# untitled.net
KiCad netlist of a schematic drawn in EAGLE
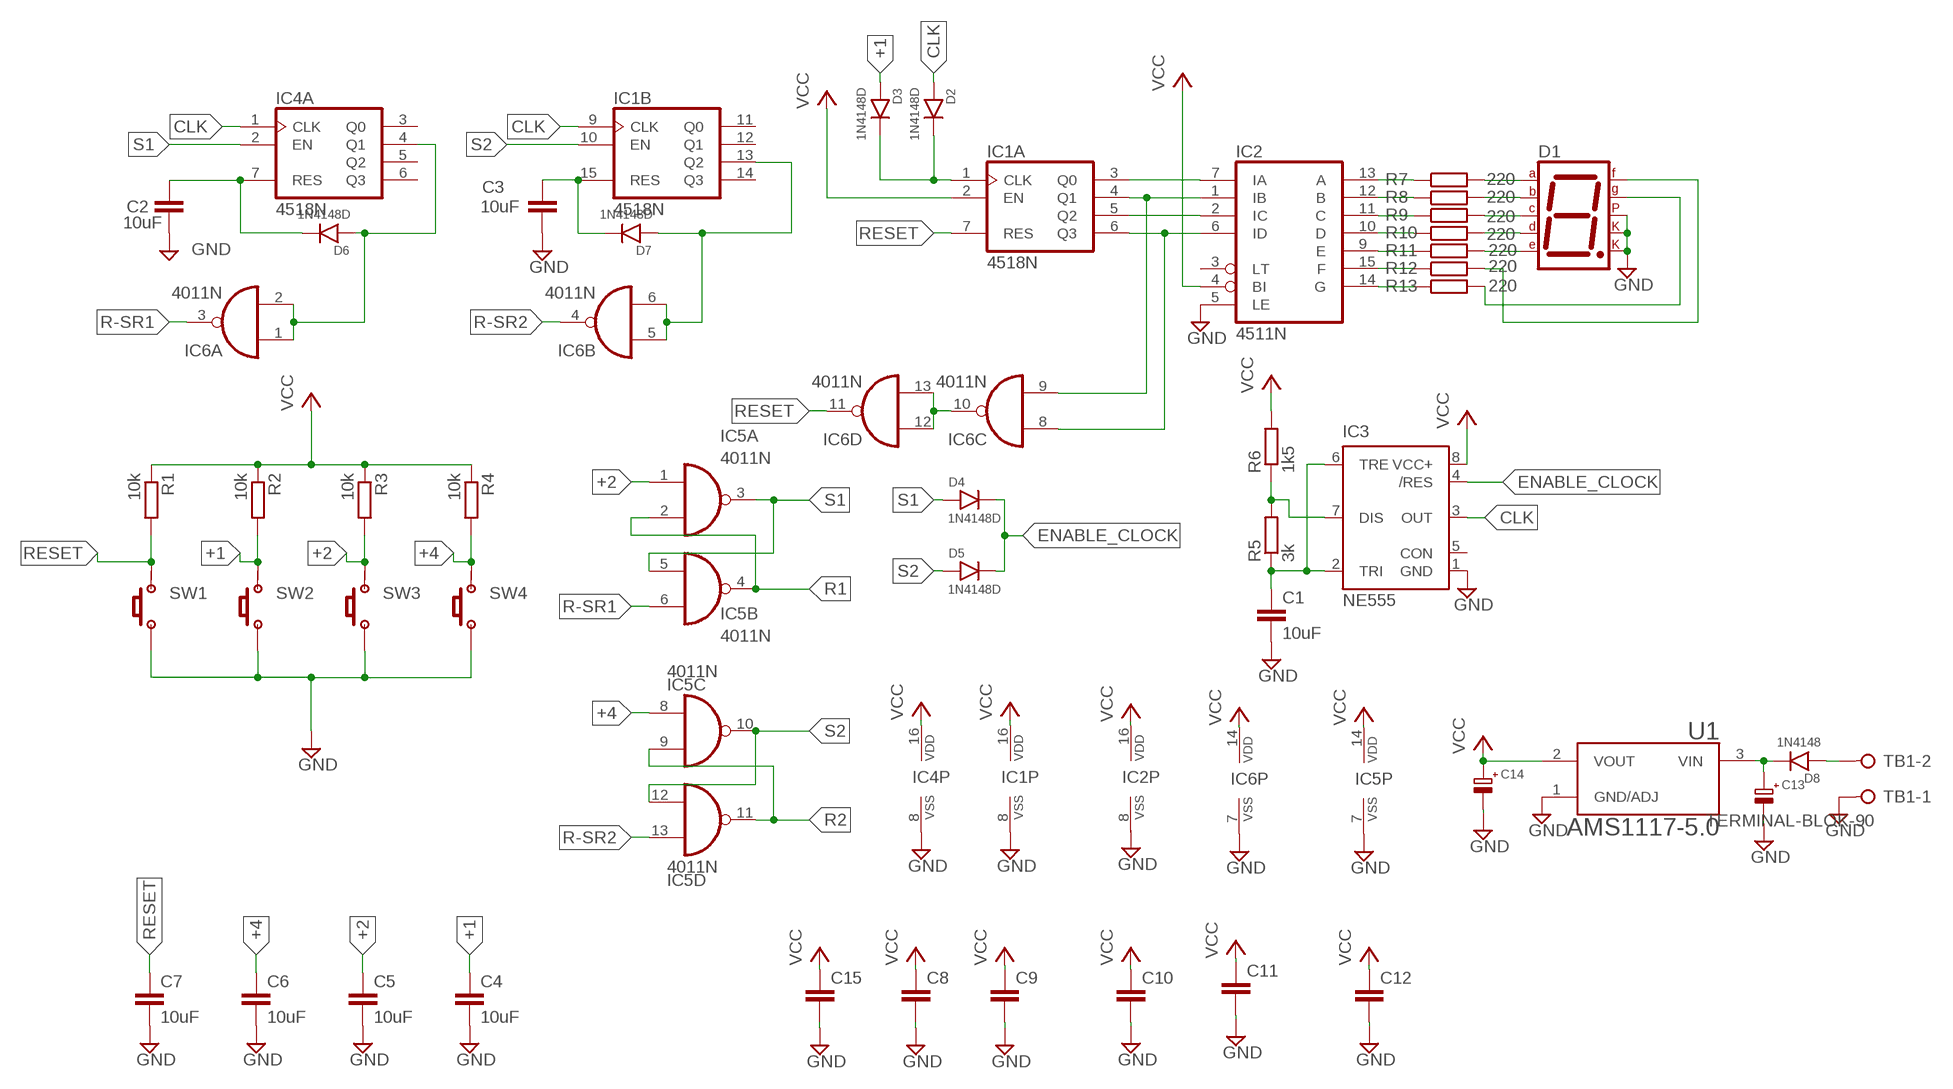
[diagram p0: schematic, sheet 1]

(export (version "E")
  (design (tool "Eeschema 10.0.6"))
  (components
    (comp (ref "C1")
      (value "10uF")
      (footprint "eagle-import:SMD0805")
      (libsource (lib "eagle-import") (part "CAP-NON0805"))
    )
    (comp (ref "C2")
      (value "10uF")
      (footprint "eagle-import:SMD0805")
      (libsource (lib "eagle-import") (part "CAP-NON0805"))
    )
    (comp (ref "C3")
      (value "10uF")
      (footprint "eagle-import:SMD0805")
      (libsource (lib "eagle-import") (part "CAP-NON0805"))
    )
    (comp (ref "C4")
      (value "10uF")
      (footprint "eagle-import:SMD0805")
      (libsource (lib "eagle-import") (part "CAP-NON0805"))
    )
    (comp (ref "C5")
      (value "10uF")
      (footprint "eagle-import:SMD0805")
      (libsource (lib "eagle-import") (part "CAP-NON0805"))
    )
    (comp (ref "C6")
      (value "10uF")
      (footprint "eagle-import:SMD0805")
      (libsource (lib "eagle-import") (part "CAP-NON0805"))
    )
    (comp (ref "C7")
      (value "10uF")
      (footprint "eagle-import:SMD0805")
      (libsource (lib "eagle-import") (part "CAP-NON0805"))
    )
    (comp (ref "C8")
      (value "CAP-NON")
      (footprint "eagle-import:MKM")
      (libsource (lib "eagle-import") (part "CAP-NON"))
    )
    (comp (ref "C9")
      (value "CAP-NON")
      (footprint "eagle-import:MKM")
      (libsource (lib "eagle-import") (part "CAP-NON"))
    )
    (comp (ref "C10")
      (value "CAP-NON")
      (footprint "eagle-import:MKM")
      (libsource (lib "eagle-import") (part "CAP-NON"))
    )
    (comp (ref "C11")
      (value "CAP-NON")
      (footprint "eagle-import:MKM")
      (libsource (lib "eagle-import") (part "CAP-NON"))
    )
    (comp (ref "C12")
      (value "CAP-NON")
      (footprint "eagle-import:MKM")
      (libsource (lib "eagle-import") (part "CAP-NON"))
    )
    (comp (ref "C13")
      (value "CAP-ELCO")
      (footprint "eagle-import:ELCO1")
      (libsource (lib "eagle-import") (part "CAP-ELCO"))
    )
    (comp (ref "C14")
      (value "CAP-ELCO")
      (footprint "eagle-import:ELCO1")
      (libsource (lib "eagle-import") (part "CAP-ELCO"))
    )
    (comp (ref "C15")
      (value "CAP-NON")
      (footprint "eagle-import:MKM")
      (libsource (lib "eagle-import") (part "CAP-NON"))
    )
    (comp (ref "D1")
      (value "7SEG-CK")
      (footprint "eagle-import:7SEG-13")
      (libsource (lib "eagle-import") (part "7SEG-CK"))
    )
    (comp (ref "D2")
      (value "1N4148D")
      (footprint "eagle-import:SOD80C")
      (libsource (lib "eagle-import") (part "1N4148D"))
    )
    (comp (ref "D3")
      (value "1N4148D")
      (footprint "eagle-import:SOD80C")
      (libsource (lib "eagle-import") (part "1N4148D"))
    )
    (comp (ref "D4")
      (value "1N4148D")
      (footprint "eagle-import:SOD80C")
      (libsource (lib "eagle-import") (part "1N4148D"))
    )
    (comp (ref "D5")
      (value "1N4148D")
      (footprint "eagle-import:SOD80C")
      (libsource (lib "eagle-import") (part "1N4148D"))
    )
    (comp (ref "D6")
      (value "1N4148D")
      (footprint "eagle-import:SOD80C")
      (libsource (lib "eagle-import") (part "1N4148D"))
    )
    (comp (ref "D7")
      (value "1N4148D")
      (footprint "eagle-import:SOD80C")
      (libsource (lib "eagle-import") (part "1N4148D"))
    )
    (comp (ref "D8")
      (value "1N4148")
      (footprint "eagle-import:DIODE")
      (libsource (lib "eagle-import") (part "1N4148"))
    )
    (comp (ref "IC1")
      (value "4518N")
      (footprint "eagle-import:DIL16")
      (libsource (lib "eagle-import") (part "4518N"))
    )
    (comp (ref "IC2")
      (value "4511N")
      (footprint "eagle-import:DIL16")
      (libsource (lib "eagle-import") (part "4511N"))
    )
    (comp (ref "IC3")
      (value "NE555")
      (footprint "eagle-import:DIL-08")
      (fields (field (name "MF") "Arrow Electronics") (field (name "MPN") "NE555N"))
      (libsource (lib "eagle-import") (part "NE555"))
    )
    (comp (ref "IC4")
      (value "4518N")
      (footprint "eagle-import:DIL16")
      (libsource (lib "eagle-import") (part "4518N"))
    )
    (comp (ref "IC5")
      (value "4011N")
      (footprint "eagle-import:DIL14")
      (libsource (lib "eagle-import") (part "4011N"))
    )
    (comp (ref "IC6")
      (value "4011N")
      (footprint "eagle-import:DIL14")
      (libsource (lib "eagle-import") (part "4011N"))
    )
    (comp (ref "R1")
      (value "10k")
      (footprint "eagle-import:SMD0805")
      (libsource (lib "eagle-import") (part "RES0805"))
    )
    (comp (ref "R2")
      (value "10k")
      (footprint "eagle-import:SMD0805")
      (libsource (lib "eagle-import") (part "RES0805"))
    )
    (comp (ref "R3")
      (value "10k")
      (footprint "eagle-import:SMD0805")
      (libsource (lib "eagle-import") (part "RES0805"))
    )
    (comp (ref "R4")
      (value "10k")
      (footprint "eagle-import:SMD0805")
      (libsource (lib "eagle-import") (part "RES0805"))
    )
    (comp (ref "R5")
      (value "3k")
      (footprint "eagle-import:SMD0805")
      (libsource (lib "eagle-import") (part "RES0805"))
    )
    (comp (ref "R6")
      (value "1k5")
      (footprint "eagle-import:SMD0805")
      (libsource (lib "eagle-import") (part "RES0805"))
    )
    (comp (ref "R7")
      (value "220")
      (footprint "eagle-import:SMD0805")
      (libsource (lib "eagle-import") (part "RES0805"))
    )
    (comp (ref "R8")
      (value "220")
      (footprint "eagle-import:SMD0805")
      (libsource (lib "eagle-import") (part "RES0805"))
    )
    (comp (ref "R9")
      (value "220")
      (footprint "eagle-import:SMD0805")
      (libsource (lib "eagle-import") (part "RES0805"))
    )
    (comp (ref "R10")
      (value "220")
      (footprint "eagle-import:SMD0805")
      (libsource (lib "eagle-import") (part "RES0805"))
    )
    (comp (ref "R11")
      (value "220")
      (footprint "eagle-import:SMD0805")
      (libsource (lib "eagle-import") (part "RES0805"))
    )
    (comp (ref "R12")
      (value "220")
      (footprint "eagle-import:SMD0805")
      (libsource (lib "eagle-import") (part "RES0805"))
    )
    (comp (ref "R13")
      (value "220")
      (footprint "eagle-import:SMD0805")
      (libsource (lib "eagle-import") (part "RES0805"))
    )
    (comp (ref "SW1")
      (value "PUSH_BUTTON4P")
      (footprint "eagle-import:PUSH_BUTTON_4P")
      (libsource (lib "eagle-import") (part "PUSH_BUTTON4P"))
    )
    (comp (ref "SW2")
      (value "PUSH_BUTTON4P")
      (footprint "eagle-import:PUSH_BUTTON_4P")
      (libsource (lib "eagle-import") (part "PUSH_BUTTON4P"))
    )
    (comp (ref "SW3")
      (value "PUSH_BUTTON4P")
      (footprint "eagle-import:PUSH_BUTTON_4P")
      (libsource (lib "eagle-import") (part "PUSH_BUTTON4P"))
    )
    (comp (ref "SW4")
      (value "PUSH_BUTTON4P")
      (footprint "eagle-import:PUSH_BUTTON_4P")
      (libsource (lib "eagle-import") (part "PUSH_BUTTON4P"))
    )
    (comp (ref "TB1")
      (value "TERMINAL-BLOK-90")
      (footprint "eagle-import:MSTBA2")
      (libsource (lib "eagle-import") (part "TERMINAL-BLOK-90"))
    )
    (comp (ref "U1")
      (value "AMS1117-5.0")
      (footprint "eagle-import:SOT229P700X180-4N")
      (libsource (lib "eagle-import") (part "AMS1117-5.0"))
    )
  )
  (nets
    (net (code "1") (name "+1") (class "Default")
      (node (ref "C4") (pin "1") (pinfunction "1_1") (pintype "passive"))
      (node (ref "D3") (pin "A") (pinfunction "1_A") (pintype "bidirectional"))
      (node (ref "R2") (pin "2") (pinfunction "2_2") (pintype "passive"))
      (node (ref "SW2") (pin "3") (pinfunction "2_3") (pintype "bidirectional"))
      (node (ref "SW2") (pin "4") (pinfunction "2_4") (pintype "bidirectional"))
    )
    (net (code "2") (name "+2") (class "Default")
      (node (ref "C5") (pin "1") (pinfunction "1_1") (pintype "passive"))
      (node (ref "IC5") (pin "1") (pinfunction "I0_1") (pintype "input"))
      (node (ref "R3") (pin "2") (pinfunction "2_2") (pintype "passive"))
      (node (ref "SW3") (pin "3") (pinfunction "2_3") (pintype "bidirectional"))
      (node (ref "SW3") (pin "4") (pinfunction "2_4") (pintype "bidirectional"))
    )
    (net (code "3") (name "+4") (class "Default")
      (node (ref "C6") (pin "1") (pinfunction "1_1") (pintype "passive"))
      (node (ref "IC5") (pin "8") (pinfunction "I0_8") (pintype "input"))
      (node (ref "R4") (pin "2") (pinfunction "2_2") (pintype "passive"))
      (node (ref "SW4") (pin "3") (pinfunction "2_3") (pintype "bidirectional"))
      (node (ref "SW4") (pin "4") (pinfunction "2_4") (pintype "bidirectional"))
    )
    (net (code "4") (name "/VSS") (class "Default")
      (node (ref "IC2") (pin "8") (pinfunction "VSS_8") (pintype "power_in"))
    )
    (net (code "5") (name "CLK") (class "Default")
      (node (ref "D2") (pin "A") (pinfunction "1_A") (pintype "bidirectional"))
      (node (ref "IC1") (pin "9") (pinfunction "CLK_9") (pintype "input"))
      (node (ref "IC3") (pin "3") (pinfunction "OUT_3") (pintype "output"))
      (node (ref "IC4") (pin "1") (pinfunction "CLK_1") (pintype "input"))
    )
    (net (code "6") (name "ENABLE_CLOCK") (class "Default")
      (node (ref "D4") (pin "C") (pinfunction "2_C") (pintype "bidirectional"))
      (node (ref "D5") (pin "C") (pinfunction "2_C") (pintype "bidirectional"))
      (node (ref "IC3") (pin "4") (pinfunction "/RES_4") (pintype "input"))
    )
    (net (code "7") (name "GND") (class "Default")
      (node (ref "C1") (pin "2") (pinfunction "2_2") (pintype "passive"))
      (node (ref "C10") (pin "2") (pinfunction "2_2") (pintype "passive"))
      (node (ref "C11") (pin "2") (pinfunction "2_2") (pintype "passive"))
      (node (ref "C12") (pin "2") (pinfunction "2_2") (pintype "passive"))
      (node (ref "C13") (pin "2") (pinfunction "2_2") (pintype "bidirectional"))
      (node (ref "C14") (pin "2") (pinfunction "2_2") (pintype "bidirectional"))
      (node (ref "C15") (pin "2") (pinfunction "2_2") (pintype "passive"))
      (node (ref "C2") (pin "2") (pinfunction "2_2") (pintype "passive"))
      (node (ref "C3") (pin "2") (pinfunction "2_2") (pintype "passive"))
      (node (ref "C4") (pin "2") (pinfunction "2_2") (pintype "passive"))
      (node (ref "C5") (pin "2") (pinfunction "2_2") (pintype "passive"))
      (node (ref "C6") (pin "2") (pinfunction "2_2") (pintype "passive"))
      (node (ref "C7") (pin "2") (pinfunction "2_2") (pintype "passive"))
      (node (ref "C8") (pin "2") (pinfunction "2_2") (pintype "passive"))
      (node (ref "C9") (pin "2") (pinfunction "2_2") (pintype "passive"))
      (node (ref "D1") (pin "3") (pinfunction "CK1_3") (pintype "passive"))
      (node (ref "D1") (pin "5") (pinfunction "DP_5") (pintype "passive"))
      (node (ref "D1") (pin "8") (pinfunction "CK2_8") (pintype "passive"))
      (node (ref "IC1") (pin "8") (pinfunction "VSS_8") (pintype "power_in"))
      (node (ref "IC2") (pin "5") (pinfunction "LE_5") (pintype "input"))
      (node (ref "IC3") (pin "1") (pinfunction "GND_1") (pintype "power_in"))
      (node (ref "IC4") (pin "8") (pinfunction "VSS_8") (pintype "power_in"))
      (node (ref "IC5") (pin "7") (pinfunction "VSS_7") (pintype "power_in"))
      (node (ref "IC6") (pin "7") (pinfunction "VSS_7") (pintype "power_in"))
      (node (ref "SW1") (pin "1") (pinfunction "1_1") (pintype "bidirectional"))
      (node (ref "SW1") (pin "2") (pinfunction "1_2") (pintype "bidirectional"))
      (node (ref "SW2") (pin "1") (pinfunction "1_1") (pintype "bidirectional"))
      (node (ref "SW2") (pin "2") (pinfunction "1_2") (pintype "bidirectional"))
      (node (ref "SW3") (pin "1") (pinfunction "1_1") (pintype "bidirectional"))
      (node (ref "SW3") (pin "2") (pinfunction "1_2") (pintype "bidirectional"))
      (node (ref "SW4") (pin "1") (pinfunction "1_1") (pintype "bidirectional"))
      (node (ref "SW4") (pin "2") (pinfunction "1_2") (pintype "bidirectional"))
      (node (ref "TB1") (pin "1") (pinfunction "KL_1") (pintype "passive"))
      (node (ref "U1") (pin "1") (pinfunction "GND/ADJ_1") (pintype "power_in"))
    )
    (net (code "8") (name "Net-(D1-A)") (class "Default")
      (node (ref "D1") (pin "7") (pinfunction "A_7") (pintype "passive"))
      (node (ref "R7") (pin "2") (pinfunction "2_2") (pintype "passive"))
    )
    (net (code "9") (name "Net-(D1-B)") (class "Default")
      (node (ref "D1") (pin "6") (pinfunction "B_6") (pintype "passive"))
      (node (ref "R8") (pin "2") (pinfunction "2_2") (pintype "passive"))
    )
    (net (code "10") (name "Net-(D1-C)") (class "Default")
      (node (ref "D1") (pin "4") (pinfunction "C_4") (pintype "passive"))
      (node (ref "R9") (pin "2") (pinfunction "2_2") (pintype "passive"))
    )
    (net (code "11") (name "Net-(D1-D)") (class "Default")
      (node (ref "D1") (pin "2") (pinfunction "D_2") (pintype "passive"))
      (node (ref "R10") (pin "2") (pinfunction "2_2") (pintype "passive"))
    )
    (net (code "12") (name "Net-(D1-E)") (class "Default")
      (node (ref "D1") (pin "1") (pinfunction "E_1") (pintype "passive"))
      (node (ref "R11") (pin "2") (pinfunction "2_2") (pintype "passive"))
    )
    (net (code "13") (name "Net-(D1-F)") (class "Default")
      (node (ref "D1") (pin "9") (pinfunction "F_9") (pintype "passive"))
      (node (ref "R12") (pin "2") (pinfunction "2_2") (pintype "passive"))
    )
    (net (code "14") (name "Net-(D1-G)") (class "Default")
      (node (ref "D1") (pin "10") (pinfunction "G_10") (pintype "passive"))
      (node (ref "R13") (pin "2") (pinfunction "2_2") (pintype "passive"))
    )
    (net (code "15") (name "Net-(D2-2)") (class "Default")
      (node (ref "D2") (pin "C") (pinfunction "2_C") (pintype "bidirectional"))
      (node (ref "D3") (pin "C") (pinfunction "2_C") (pintype "bidirectional"))
      (node (ref "IC1") (pin "1") (pinfunction "CLK_1") (pintype "input"))
    )
    (net (code "16") (name "Net-(D6-1)") (class "Default")
      (node (ref "D6") (pin "A") (pinfunction "1_A") (pintype "bidirectional"))
      (node (ref "IC4") (pin "4") (pinfunction "Q1_4") (pintype "output"))
      (node (ref "IC6") (pin "1") (pinfunction "I0_1") (pintype "input"))
      (node (ref "IC6") (pin "2") (pinfunction "I1_2") (pintype "input"))
    )
    (net (code "17") (name "Net-(D6-2)") (class "Default")
      (node (ref "C2") (pin "1") (pinfunction "1_1") (pintype "passive"))
      (node (ref "D6") (pin "C") (pinfunction "2_C") (pintype "bidirectional"))
      (node (ref "IC4") (pin "7") (pinfunction "RES_7") (pintype "input"))
    )
    (net (code "18") (name "Net-(D7-1)") (class "Default")
      (node (ref "D7") (pin "A") (pinfunction "1_A") (pintype "bidirectional"))
      (node (ref "IC1") (pin "13") (pinfunction "Q2_13") (pintype "output"))
      (node (ref "IC6") (pin "5") (pinfunction "I0_5") (pintype "input"))
      (node (ref "IC6") (pin "6") (pinfunction "I1_6") (pintype "input"))
    )
    (net (code "19") (name "Net-(D7-2)") (class "Default")
      (node (ref "C3") (pin "1") (pinfunction "1_1") (pintype "passive"))
      (node (ref "D7") (pin "C") (pinfunction "2_C") (pintype "bidirectional"))
      (node (ref "IC1") (pin "15") (pinfunction "RES_15") (pintype "input"))
    )
    (net (code "20") (name "Net-(IC1A-Q0)") (class "Default")
      (node (ref "IC1") (pin "3") (pinfunction "Q0_3") (pintype "output"))
      (node (ref "IC2") (pin "7") (pinfunction "IA_7") (pintype "input"))
    )
    (net (code "21") (name "Net-(IC1A-Q1)") (class "Default")
      (node (ref "IC1") (pin "4") (pinfunction "Q1_4") (pintype "output"))
      (node (ref "IC2") (pin "1") (pinfunction "IB_1") (pintype "input"))
      (node (ref "IC6") (pin "9") (pinfunction "I1_9") (pintype "input"))
    )
    (net (code "22") (name "Net-(IC1A-Q2)") (class "Default")
      (node (ref "IC1") (pin "5") (pinfunction "Q2_5") (pintype "output"))
      (node (ref "IC2") (pin "2") (pinfunction "IC_2") (pintype "input"))
    )
    (net (code "23") (name "Net-(IC1A-Q3)") (class "Default")
      (node (ref "IC1") (pin "6") (pinfunction "Q3_6") (pintype "output"))
      (node (ref "IC2") (pin "6") (pinfunction "ID_6") (pintype "input"))
      (node (ref "IC6") (pin "8") (pinfunction "I0_8") (pintype "input"))
    )
    (net (code "24") (name "Net-(IC2A-A)") (class "Default")
      (node (ref "IC2") (pin "13") (pinfunction "A_13") (pintype "output"))
      (node (ref "R7") (pin "1") (pinfunction "1_1") (pintype "passive"))
    )
    (net (code "25") (name "Net-(IC2A-B)") (class "Default")
      (node (ref "IC2") (pin "12") (pinfunction "B_12") (pintype "output"))
      (node (ref "R8") (pin "1") (pinfunction "1_1") (pintype "passive"))
    )
    (net (code "26") (name "Net-(IC2A-C)") (class "Default")
      (node (ref "IC2") (pin "11") (pinfunction "C_11") (pintype "output"))
      (node (ref "R9") (pin "1") (pinfunction "1_1") (pintype "passive"))
    )
    (net (code "27") (name "Net-(IC2A-D)") (class "Default")
      (node (ref "IC2") (pin "10") (pinfunction "D_10") (pintype "output"))
      (node (ref "R10") (pin "1") (pinfunction "1_1") (pintype "passive"))
    )
    (net (code "28") (name "Net-(IC2A-E)") (class "Default")
      (node (ref "IC2") (pin "9") (pinfunction "E_9") (pintype "output"))
      (node (ref "R11") (pin "1") (pinfunction "1_1") (pintype "passive"))
    )
    (net (code "29") (name "Net-(IC2A-F)") (class "Default")
      (node (ref "IC2") (pin "15") (pinfunction "F_15") (pintype "output"))
      (node (ref "R12") (pin "1") (pinfunction "1_1") (pintype "passive"))
    )
    (net (code "30") (name "Net-(IC2A-G)") (class "Default")
      (node (ref "IC2") (pin "14") (pinfunction "G_14") (pintype "output"))
      (node (ref "R13") (pin "1") (pinfunction "1_1") (pintype "passive"))
    )
    (net (code "31") (name "Net-(IC3-DIS)") (class "Default")
      (node (ref "IC3") (pin "7") (pinfunction "DIS_7") (pintype "input"))
      (node (ref "R5") (pin "2") (pinfunction "2_2") (pintype "passive"))
      (node (ref "R6") (pin "1") (pinfunction "1_1") (pintype "passive"))
    )
    (net (code "32") (name "Net-(IC3-TRE)") (class "Default")
      (node (ref "C1") (pin "1") (pinfunction "1_1") (pintype "passive"))
      (node (ref "IC3") (pin "2") (pinfunction "TRI_2") (pintype "input"))
      (node (ref "IC3") (pin "6") (pinfunction "TRE_6") (pintype "input"))
      (node (ref "R5") (pin "1") (pinfunction "1_1") (pintype "passive"))
    )
    (net (code "33") (name "Net-(IC6C-O)") (class "Default")
      (node (ref "IC6") (pin "10") (pinfunction "O_10") (pintype "output"))
      (node (ref "IC6") (pin "12") (pinfunction "I0_12") (pintype "input"))
      (node (ref "IC6") (pin "13") (pinfunction "I1_13") (pintype "input"))
    )
    (net (code "34") (name "Net-(TB1B-KL)") (class "Default")
      (node (ref "D8") (pin "1") (pinfunction "1_1") (pintype "bidirectional"))
      (node (ref "TB1") (pin "2") (pinfunction "KL_2") (pintype "passive"))
    )
    (net (code "35") (name "Net-(U1-VIN)") (class "Default")
      (node (ref "C13") (pin "1") (pinfunction "1_1") (pintype "bidirectional"))
      (node (ref "D8") (pin "2") (pinfunction "2_2") (pintype "bidirectional"))
      (node (ref "U1") (pin "3") (pinfunction "VIN_3") (pintype "input"))
    )
    (net (code "36") (name "R-SR1") (class "Default")
      (node (ref "IC5") (pin "6") (pinfunction "I1_6") (pintype "input"))
      (node (ref "IC6") (pin "3") (pinfunction "O_3") (pintype "output"))
    )
    (net (code "37") (name "R-SR2") (class "Default")
      (node (ref "IC5") (pin "13") (pinfunction "I1_13") (pintype "input"))
      (node (ref "IC6") (pin "4") (pinfunction "O_4") (pintype "output"))
    )
    (net (code "38") (name "R1") (class "Default")
      (node (ref "IC5") (pin "2") (pinfunction "I1_2") (pintype "input"))
      (node (ref "IC5") (pin "4") (pinfunction "O_4") (pintype "output"))
    )
    (net (code "39") (name "R2") (class "Default")
      (node (ref "IC5") (pin "11") (pinfunction "O_11") (pintype "output"))
      (node (ref "IC5") (pin "9") (pinfunction "I1_9") (pintype "input"))
    )
    (net (code "40") (name "RESET") (class "Default")
      (node (ref "C7") (pin "1") (pinfunction "1_1") (pintype "passive"))
      (node (ref "IC1") (pin "7") (pinfunction "RES_7") (pintype "input"))
      (node (ref "IC6") (pin "11") (pinfunction "O_11") (pintype "output"))
      (node (ref "R1") (pin "2") (pinfunction "2_2") (pintype "passive"))
      (node (ref "SW1") (pin "3") (pinfunction "2_3") (pintype "bidirectional"))
      (node (ref "SW1") (pin "4") (pinfunction "2_4") (pintype "bidirectional"))
    )
    (net (code "41") (name "S1") (class "Default")
      (node (ref "D4") (pin "A") (pinfunction "1_A") (pintype "bidirectional"))
      (node (ref "IC4") (pin "2") (pinfunction "EN_2") (pintype "input"))
      (node (ref "IC5") (pin "3") (pinfunction "O_3") (pintype "output"))
      (node (ref "IC5") (pin "5") (pinfunction "I0_5") (pintype "input"))
    )
    (net (code "42") (name "S2") (class "Default")
      (node (ref "D5") (pin "A") (pinfunction "1_A") (pintype "bidirectional"))
      (node (ref "IC1") (pin "10") (pinfunction "EN_10") (pintype "input"))
      (node (ref "IC5") (pin "10") (pinfunction "O_10") (pintype "output"))
      (node (ref "IC5") (pin "12") (pinfunction "I0_12") (pintype "input"))
    )
    (net (code "43") (name "VCC") (class "Default")
      (node (ref "C10") (pin "1") (pinfunction "1_1") (pintype "passive"))
      (node (ref "C11") (pin "1") (pinfunction "1_1") (pintype "passive"))
      (node (ref "C12") (pin "1") (pinfunction "1_1") (pintype "passive"))
      (node (ref "C14") (pin "1") (pinfunction "1_1") (pintype "bidirectional"))
      (node (ref "C15") (pin "1") (pinfunction "1_1") (pintype "passive"))
      (node (ref "C8") (pin "1") (pinfunction "1_1") (pintype "passive"))
      (node (ref "C9") (pin "1") (pinfunction "1_1") (pintype "passive"))
      (node (ref "IC1") (pin "16") (pinfunction "VDD_16") (pintype "power_in"))
      (node (ref "IC1") (pin "2") (pinfunction "EN_2") (pintype "input"))
      (node (ref "IC2") (pin "16") (pinfunction "VDD_16") (pintype "power_in"))
      (node (ref "IC2") (pin "4") (pinfunction "BI_4") (pintype "input"))
      (node (ref "IC3") (pin "8") (pinfunction "VCC+_8") (pintype "power_in"))
      (node (ref "IC4") (pin "16") (pinfunction "VDD_16") (pintype "power_in"))
      (node (ref "IC5") (pin "14") (pinfunction "VDD_14") (pintype "power_in"))
      (node (ref "IC6") (pin "14") (pinfunction "VDD_14") (pintype "power_in"))
      (node (ref "R1") (pin "1") (pinfunction "1_1") (pintype "passive"))
      (node (ref "R2") (pin "1") (pinfunction "1_1") (pintype "passive"))
      (node (ref "R3") (pin "1") (pinfunction "1_1") (pintype "passive"))
      (node (ref "R4") (pin "1") (pinfunction "1_1") (pintype "passive"))
      (node (ref "R6") (pin "2") (pinfunction "2_2") (pintype "passive"))
      (node (ref "U1") (pin "2") (pinfunction "VOUT_2") (pintype "output"))
    )
    (net (code "44") (name "unconnected-(IC1B-Q0-Pad11)") (class "Default")
      (node (ref "IC1") (pin "11") (pinfunction "Q0_11") (pintype "output"))
    )
    (net (code "45") (name "unconnected-(IC1B-Q1-Pad12)") (class "Default")
      (node (ref "IC1") (pin "12") (pinfunction "Q1_12") (pintype "output"))
    )
    (net (code "46") (name "unconnected-(IC1B-Q3-Pad14)") (class "Default")
      (node (ref "IC1") (pin "14") (pinfunction "Q3_14") (pintype "output"))
    )
    (net (code "47") (name "unconnected-(IC2A-LT-Pad3)") (class "Default")
      (node (ref "IC2") (pin "3") (pinfunction "LT_3") (pintype "input"))
    )
    (net (code "48") (name "unconnected-(IC3-CON-Pad5)") (class "Default")
      (node (ref "IC3") (pin "5") (pinfunction "CON_5") (pintype "input"))
    )
    (net (code "49") (name "unconnected-(IC4A-Q0-Pad3)") (class "Default")
      (node (ref "IC4") (pin "3") (pinfunction "Q0_3") (pintype "output"))
    )
    (net (code "50") (name "unconnected-(IC4A-Q2-Pad5)") (class "Default")
      (node (ref "IC4") (pin "5") (pinfunction "Q2_5") (pintype "output"))
    )
    (net (code "51") (name "unconnected-(IC4A-Q3-Pad6)") (class "Default")
      (node (ref "IC4") (pin "6") (pinfunction "Q3_6") (pintype "output"))
    )
  )
)
